# ospy_hw3_3_extensions.net
KiCad netlist of a schematic drawn in EAGLE
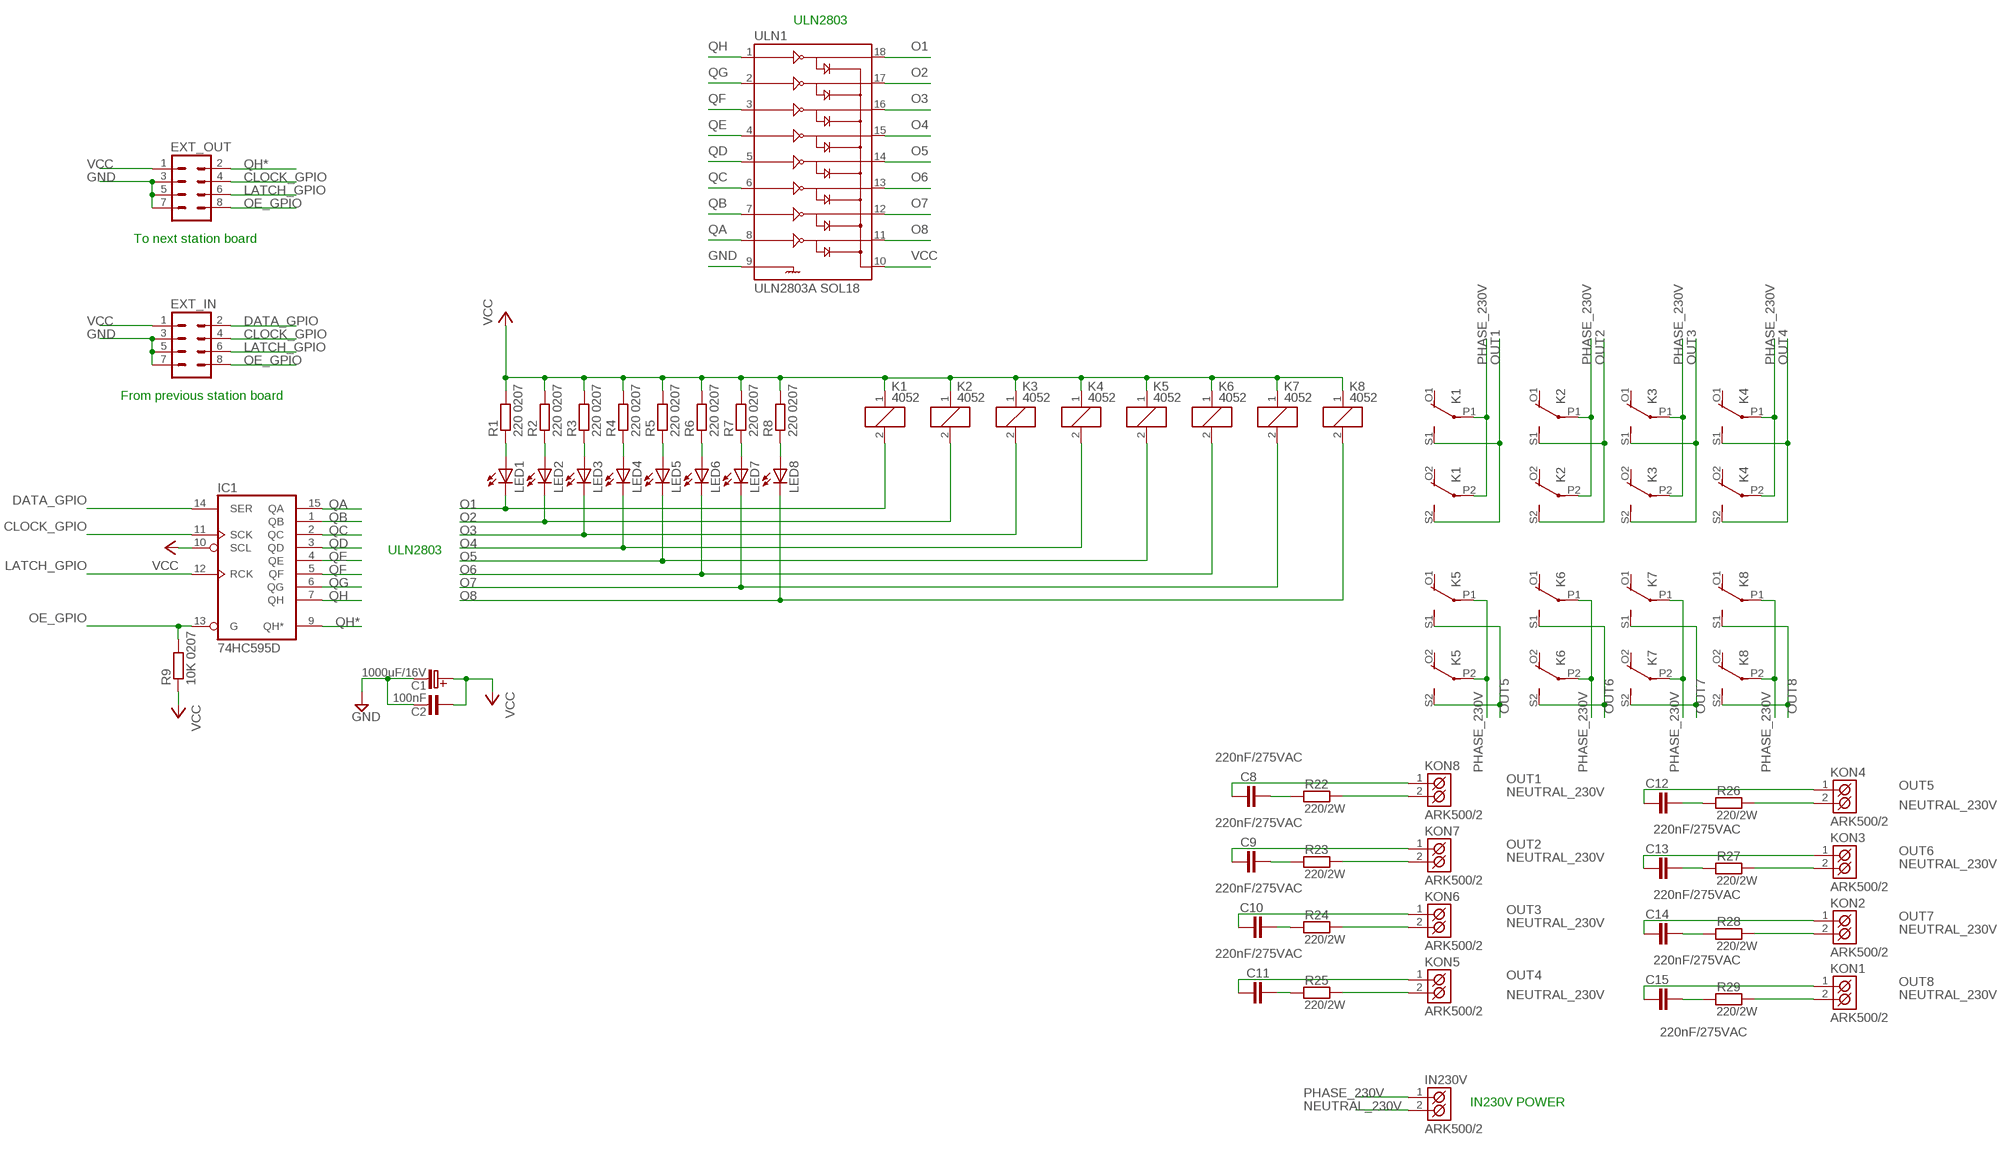
[diagram p0: schematic, sheet 1]

(export (version "E")
  (design (tool "Eeschema 10.0.6"))
  (components
    (comp (ref "C1")
      (value "1000uF/16V")
      (footprint "eagle-import:C_EL_5")
      (libsource (lib "eagle-import") (part "#_RADIAL_POUZDRA5"))
    )
    (comp (ref "C2")
      (value "100nF")
      (footprint "eagle-import:RM5_2,5")
      (libsource (lib "eagle-import") (part "100N-J/63V"))
    )
    (comp (ref "C8")
      (value "220nF/275VAC")
      (footprint "eagle-import:C225-087X268")
      (libsource (lib "eagle-import") (part "C-EU225-087X268"))
    )
    (comp (ref "C9")
      (value "220nF/275VAC")
      (footprint "eagle-import:C225-087X268")
      (libsource (lib "eagle-import") (part "C-EU225-087X268"))
    )
    (comp (ref "C10")
      (value "220nF/275VAC")
      (footprint "eagle-import:C225-087X268")
      (libsource (lib "eagle-import") (part "C-EU225-087X268"))
    )
    (comp (ref "C11")
      (value "220nF/275VAC")
      (footprint "eagle-import:C225-087X268")
      (libsource (lib "eagle-import") (part "C-EU225-087X268"))
    )
    (comp (ref "C12")
      (value "220nF/275VAC")
      (footprint "eagle-import:C225-087X268")
      (libsource (lib "eagle-import") (part "C-EU225-087X268"))
    )
    (comp (ref "C13")
      (value "220nF/275VAC")
      (footprint "eagle-import:C225-087X268")
      (libsource (lib "eagle-import") (part "C-EU225-087X268"))
    )
    (comp (ref "C14")
      (value "220nF/275VAC")
      (footprint "eagle-import:C225-087X268")
      (libsource (lib "eagle-import") (part "C-EU225-087X268"))
    )
    (comp (ref "C15")
      (value "220nF/275VAC")
      (footprint "eagle-import:C225-087X268")
      (libsource (lib "eagle-import") (part "C-EU225-087X268"))
    )
    (comp (ref "EXT_IN")
      (value "M04X2")
      (footprint "eagle-import:2X4")
      (libsource (lib "eagle-import") (part "M04X2"))
    )
    (comp (ref "EXT_OUT")
      (value "M04X2")
      (footprint "eagle-import:2X4")
      (libsource (lib "eagle-import") (part "M04X2"))
    )
    (comp (ref "IC1")
      (value "74HC595D")
      (footprint "eagle-import:SO16")
      (libsource (lib "eagle-import") (part "74595DHC"))
    )
    (comp (ref "IN230V")
      (value "ARK500/2")
      (footprint "eagle-import:ARK500_2")
      (libsource (lib "eagle-import") (part "ARK500/2"))
    )
    (comp (ref "K1")
      (value "4052")
      (footprint "eagle-import:F4052")
      (libsource (lib "eagle-import") (part "4052"))
    )
    (comp (ref "K2")
      (value "4052")
      (footprint "eagle-import:F4052")
      (libsource (lib "eagle-import") (part "4052"))
    )
    (comp (ref "K3")
      (value "4052")
      (footprint "eagle-import:F4052")
      (libsource (lib "eagle-import") (part "4052"))
    )
    (comp (ref "K4")
      (value "4052")
      (footprint "eagle-import:F4052")
      (libsource (lib "eagle-import") (part "4052"))
    )
    (comp (ref "K5")
      (value "4052")
      (footprint "eagle-import:F4052")
      (libsource (lib "eagle-import") (part "4052"))
    )
    (comp (ref "K6")
      (value "4052")
      (footprint "eagle-import:F4052")
      (libsource (lib "eagle-import") (part "4052"))
    )
    (comp (ref "K7")
      (value "4052")
      (footprint "eagle-import:F4052")
      (libsource (lib "eagle-import") (part "4052"))
    )
    (comp (ref "K8")
      (value "4052")
      (footprint "eagle-import:F4052")
      (libsource (lib "eagle-import") (part "4052"))
    )
    (comp (ref "KON1")
      (value "ARK500/2")
      (footprint "eagle-import:ARK500_2")
      (libsource (lib "eagle-import") (part "ARK500/2"))
    )
    (comp (ref "KON2")
      (value "ARK500/2")
      (footprint "eagle-import:ARK500_2")
      (libsource (lib "eagle-import") (part "ARK500/2"))
    )
    (comp (ref "KON3")
      (value "ARK500/2")
      (footprint "eagle-import:ARK500_2")
      (libsource (lib "eagle-import") (part "ARK500/2"))
    )
    (comp (ref "KON4")
      (value "ARK500/2")
      (footprint "eagle-import:ARK500_2")
      (libsource (lib "eagle-import") (part "ARK500/2"))
    )
    (comp (ref "KON5")
      (value "ARK500/2")
      (footprint "eagle-import:ARK500_2")
      (libsource (lib "eagle-import") (part "ARK500/2"))
    )
    (comp (ref "KON6")
      (value "ARK500/2")
      (footprint "eagle-import:ARK500_2")
      (libsource (lib "eagle-import") (part "ARK500/2"))
    )
    (comp (ref "KON7")
      (value "ARK500/2")
      (footprint "eagle-import:ARK500_2")
      (libsource (lib "eagle-import") (part "ARK500/2"))
    )
    (comp (ref "KON8")
      (value "ARK500/2")
      (footprint "eagle-import:ARK500_2")
      (libsource (lib "eagle-import") (part "ARK500/2"))
    )
    (comp (ref "LED1")
      (value "LED3MM")
      (footprint "eagle-import:LED3MM")
      (libsource (lib "eagle-import") (part "LED3MM"))
    )
    (comp (ref "LED2")
      (value "LED3MM")
      (footprint "eagle-import:LED3MM")
      (libsource (lib "eagle-import") (part "LED3MM"))
    )
    (comp (ref "LED3")
      (value "LED3MM")
      (footprint "eagle-import:LED3MM")
      (libsource (lib "eagle-import") (part "LED3MM"))
    )
    (comp (ref "LED4")
      (value "LED3MM")
      (footprint "eagle-import:LED3MM")
      (libsource (lib "eagle-import") (part "LED3MM"))
    )
    (comp (ref "LED5")
      (value "LED3MM")
      (footprint "eagle-import:LED3MM")
      (libsource (lib "eagle-import") (part "LED3MM"))
    )
    (comp (ref "LED6")
      (value "LED3MM")
      (footprint "eagle-import:LED3MM")
      (libsource (lib "eagle-import") (part "LED3MM"))
    )
    (comp (ref "LED7")
      (value "LED3MM")
      (footprint "eagle-import:LED3MM")
      (libsource (lib "eagle-import") (part "LED3MM"))
    )
    (comp (ref "LED8")
      (value "LED3MM")
      (footprint "eagle-import:LED3MM")
      (libsource (lib "eagle-import") (part "LED3MM"))
    )
    (comp (ref "R1")
      (value "220 0207")
      (footprint "eagle-import:0207_10")
      (libsource (lib "eagle-import") (part "R-EU_0207/10"))
    )
    (comp (ref "R2")
      (value "220 0207")
      (footprint "eagle-import:0207_10")
      (libsource (lib "eagle-import") (part "R-EU_0207/10"))
    )
    (comp (ref "R3")
      (value "220 0207")
      (footprint "eagle-import:0207_10")
      (libsource (lib "eagle-import") (part "R-EU_0207/10"))
    )
    (comp (ref "R4")
      (value "220 0207")
      (footprint "eagle-import:0207_10")
      (libsource (lib "eagle-import") (part "R-EU_0207/10"))
    )
    (comp (ref "R5")
      (value "220 0207")
      (footprint "eagle-import:0207_10")
      (libsource (lib "eagle-import") (part "R-EU_0207/10"))
    )
    (comp (ref "R6")
      (value "220 0207")
      (footprint "eagle-import:0207_10")
      (libsource (lib "eagle-import") (part "R-EU_0207/10"))
    )
    (comp (ref "R7")
      (value "220 0207")
      (footprint "eagle-import:0207_10")
      (libsource (lib "eagle-import") (part "R-EU_0207/10"))
    )
    (comp (ref "R8")
      (value "220 0207")
      (footprint "eagle-import:0207_10")
      (libsource (lib "eagle-import") (part "R-EU_0207/10"))
    )
    (comp (ref "R9")
      (value "10K 0207")
      (footprint "eagle-import:0207_10")
      (libsource (lib "eagle-import") (part "R-EU_0207/10"))
    )
    (comp (ref "R22")
      (value "220/2W")
      (footprint "eagle-import:R__2W")
      (libsource (lib "eagle-import") (part "W2_220R"))
    )
    (comp (ref "R23")
      (value "220/2W")
      (footprint "eagle-import:R__2W")
      (libsource (lib "eagle-import") (part "W2_220R"))
    )
    (comp (ref "R24")
      (value "220/2W")
      (footprint "eagle-import:R__2W")
      (libsource (lib "eagle-import") (part "W2_220R"))
    )
    (comp (ref "R25")
      (value "220/2W")
      (footprint "eagle-import:R__2W")
      (libsource (lib "eagle-import") (part "W2_220R"))
    )
    (comp (ref "R26")
      (value "220/2W")
      (footprint "eagle-import:R__2W")
      (libsource (lib "eagle-import") (part "W2_220R"))
    )
    (comp (ref "R27")
      (value "220/2W")
      (footprint "eagle-import:R__2W")
      (libsource (lib "eagle-import") (part "W2_220R"))
    )
    (comp (ref "R28")
      (value "220/2W")
      (footprint "eagle-import:R__2W")
      (libsource (lib "eagle-import") (part "W2_220R"))
    )
    (comp (ref "R29")
      (value "220/2W")
      (footprint "eagle-import:R__2W")
      (libsource (lib "eagle-import") (part "W2_220R"))
    )
    (comp (ref "ULN1")
      (value "ULN2803A SOL18")
      (footprint "eagle-import:SO18L")
      (libsource (lib "eagle-import") (part "ULN2803SOICW"))
    )
  )
  (nets
    (net (code "1") (name "/CLOCK_GPIO") (class "Default")
      (node (ref "EXT_IN") (pin "4") (pinfunction "4_4") (pintype "passive"))
      (node (ref "EXT_OUT") (pin "4") (pinfunction "4_4") (pintype "passive"))
      (node (ref "IC1") (pin "11") (pinfunction "SCK_11") (pintype "input"))
    )
    (net (code "2") (name "/DATA_GPIO") (class "Default")
      (node (ref "EXT_IN") (pin "2") (pinfunction "2_2") (pintype "passive"))
      (node (ref "IC1") (pin "14") (pinfunction "SER_14") (pintype "input"))
    )
    (net (code "3") (name "/LATCH_GPIO") (class "Default")
      (node (ref "EXT_IN") (pin "6") (pinfunction "6_6") (pintype "passive"))
      (node (ref "EXT_OUT") (pin "6") (pinfunction "6_6") (pintype "passive"))
      (node (ref "IC1") (pin "12") (pinfunction "RCK_12") (pintype "input"))
    )
    (net (code "4") (name "/NEUTRAL_230V") (class "Default")
      (node (ref "IN230V") (pin "2") (pinfunction "K2_2") (pintype "passive"))
      (node (ref "KON1") (pin "2") (pinfunction "K2_2") (pintype "passive"))
      (node (ref "KON2") (pin "2") (pinfunction "K2_2") (pintype "passive"))
      (node (ref "KON3") (pin "2") (pinfunction "K2_2") (pintype "passive"))
      (node (ref "KON4") (pin "2") (pinfunction "K2_2") (pintype "passive"))
      (node (ref "KON5") (pin "2") (pinfunction "K2_2") (pintype "passive"))
      (node (ref "KON6") (pin "2") (pinfunction "K2_2") (pintype "passive"))
      (node (ref "KON7") (pin "2") (pinfunction "K2_2") (pintype "passive"))
      (node (ref "KON8") (pin "2") (pinfunction "K2_2") (pintype "passive"))
      (node (ref "R22") (pin "2") (pinfunction "2_2") (pintype "passive"))
      (node (ref "R23") (pin "2") (pinfunction "2_2") (pintype "passive"))
      (node (ref "R24") (pin "2") (pinfunction "2_2") (pintype "passive"))
      (node (ref "R25") (pin "2") (pinfunction "2_2") (pintype "passive"))
      (node (ref "R26") (pin "2") (pinfunction "2_2") (pintype "passive"))
      (node (ref "R27") (pin "2") (pinfunction "2_2") (pintype "passive"))
      (node (ref "R28") (pin "2") (pinfunction "2_2") (pintype "passive"))
      (node (ref "R29") (pin "2") (pinfunction "2_2") (pintype "passive"))
    )
    (net (code "5") (name "/O1") (class "Default")
      (node (ref "K1") (pin "2") (pinfunction "2_2") (pintype "passive"))
      (node (ref "LED1") (pin "K") (pinfunction "C_K") (pintype "passive"))
      (node (ref "ULN1") (pin "18") (pinfunction "18_18") (pintype "bidirectional"))
    )
    (net (code "6") (name "/O2") (class "Default")
      (node (ref "K2") (pin "2") (pinfunction "2_2") (pintype "passive"))
      (node (ref "LED2") (pin "K") (pinfunction "C_K") (pintype "passive"))
      (node (ref "ULN1") (pin "17") (pinfunction "17_17") (pintype "bidirectional"))
    )
    (net (code "7") (name "/O3") (class "Default")
      (node (ref "K3") (pin "2") (pinfunction "2_2") (pintype "passive"))
      (node (ref "LED3") (pin "K") (pinfunction "C_K") (pintype "passive"))
      (node (ref "ULN1") (pin "16") (pinfunction "16_16") (pintype "bidirectional"))
    )
    (net (code "8") (name "/O4") (class "Default")
      (node (ref "K4") (pin "2") (pinfunction "2_2") (pintype "passive"))
      (node (ref "LED4") (pin "K") (pinfunction "C_K") (pintype "passive"))
      (node (ref "ULN1") (pin "15") (pinfunction "15_15") (pintype "bidirectional"))
    )
    (net (code "9") (name "/O5") (class "Default")
      (node (ref "K5") (pin "2") (pinfunction "2_2") (pintype "passive"))
      (node (ref "LED5") (pin "K") (pinfunction "C_K") (pintype "passive"))
      (node (ref "ULN1") (pin "14") (pinfunction "14_14") (pintype "bidirectional"))
    )
    (net (code "10") (name "/O6") (class "Default")
      (node (ref "K6") (pin "2") (pinfunction "2_2") (pintype "passive"))
      (node (ref "LED6") (pin "K") (pinfunction "C_K") (pintype "passive"))
      (node (ref "ULN1") (pin "13") (pinfunction "13_13") (pintype "bidirectional"))
    )
    (net (code "11") (name "/O7") (class "Default")
      (node (ref "K7") (pin "2") (pinfunction "2_2") (pintype "passive"))
      (node (ref "LED7") (pin "K") (pinfunction "C_K") (pintype "passive"))
      (node (ref "ULN1") (pin "12") (pinfunction "12_12") (pintype "bidirectional"))
    )
    (net (code "12") (name "/O8") (class "Default")
      (node (ref "K8") (pin "2") (pinfunction "2_2") (pintype "passive"))
      (node (ref "LED8") (pin "K") (pinfunction "C_K") (pintype "passive"))
      (node (ref "ULN1") (pin "11") (pinfunction "11_11") (pintype "bidirectional"))
    )
    (net (code "13") (name "/OE_GPIO") (class "Default")
      (node (ref "EXT_IN") (pin "8") (pinfunction "8_8") (pintype "passive"))
      (node (ref "EXT_OUT") (pin "8") (pinfunction "8_8") (pintype "passive"))
      (node (ref "IC1") (pin "13") (pinfunction "G_13") (pintype "input"))
      (node (ref "R9") (pin "2") (pinfunction "2_2") (pintype "passive"))
    )
    (net (code "14") (name "/OUT1") (class "Default")
      (node (ref "C8") (pin "1") (pinfunction "1_1") (pintype "passive"))
      (node (ref "K1") (pin "S1") (pinfunction "S_S1") (pintype "passive"))
      (node (ref "K1") (pin "S2") (pinfunction "S_S2") (pintype "passive"))
      (node (ref "KON8") (pin "1") (pinfunction "K1_1") (pintype "passive"))
    )
    (net (code "15") (name "/OUT2") (class "Default")
      (node (ref "C9") (pin "1") (pinfunction "1_1") (pintype "passive"))
      (node (ref "K2") (pin "S1") (pinfunction "S_S1") (pintype "passive"))
      (node (ref "K2") (pin "S2") (pinfunction "S_S2") (pintype "passive"))
      (node (ref "KON7") (pin "1") (pinfunction "K1_1") (pintype "passive"))
    )
    (net (code "16") (name "/OUT3") (class "Default")
      (node (ref "C10") (pin "1") (pinfunction "1_1") (pintype "passive"))
      (node (ref "K3") (pin "S1") (pinfunction "S_S1") (pintype "passive"))
      (node (ref "K3") (pin "S2") (pinfunction "S_S2") (pintype "passive"))
      (node (ref "KON6") (pin "1") (pinfunction "K1_1") (pintype "passive"))
    )
    (net (code "17") (name "/OUT4") (class "Default")
      (node (ref "C11") (pin "1") (pinfunction "1_1") (pintype "passive"))
      (node (ref "K4") (pin "S1") (pinfunction "S_S1") (pintype "passive"))
      (node (ref "K4") (pin "S2") (pinfunction "S_S2") (pintype "passive"))
      (node (ref "KON5") (pin "1") (pinfunction "K1_1") (pintype "passive"))
    )
    (net (code "18") (name "/OUT5") (class "Default")
      (node (ref "C12") (pin "1") (pinfunction "1_1") (pintype "passive"))
      (node (ref "K5") (pin "S1") (pinfunction "S_S1") (pintype "passive"))
      (node (ref "K5") (pin "S2") (pinfunction "S_S2") (pintype "passive"))
      (node (ref "KON4") (pin "1") (pinfunction "K1_1") (pintype "passive"))
    )
    (net (code "19") (name "/OUT6") (class "Default")
      (node (ref "C13") (pin "1") (pinfunction "1_1") (pintype "passive"))
      (node (ref "K6") (pin "S1") (pinfunction "S_S1") (pintype "passive"))
      (node (ref "K6") (pin "S2") (pinfunction "S_S2") (pintype "passive"))
      (node (ref "KON3") (pin "1") (pinfunction "K1_1") (pintype "passive"))
    )
    (net (code "20") (name "/OUT7") (class "Default")
      (node (ref "C14") (pin "1") (pinfunction "1_1") (pintype "passive"))
      (node (ref "K7") (pin "S1") (pinfunction "S_S1") (pintype "passive"))
      (node (ref "K7") (pin "S2") (pinfunction "S_S2") (pintype "passive"))
      (node (ref "KON2") (pin "1") (pinfunction "K1_1") (pintype "passive"))
    )
    (net (code "21") (name "/OUT8") (class "Default")
      (node (ref "C15") (pin "1") (pinfunction "1_1") (pintype "passive"))
      (node (ref "K8") (pin "S1") (pinfunction "S_S1") (pintype "passive"))
      (node (ref "K8") (pin "S2") (pinfunction "S_S2") (pintype "passive"))
      (node (ref "KON1") (pin "1") (pinfunction "K1_1") (pintype "passive"))
    )
    (net (code "22") (name "/PHASE_230V") (class "Default")
      (node (ref "IN230V") (pin "1") (pinfunction "K1_1") (pintype "passive"))
      (node (ref "K1") (pin "P1") (pinfunction "P_P1") (pintype "passive"))
      (node (ref "K1") (pin "P2") (pinfunction "P_P2") (pintype "passive"))
      (node (ref "K2") (pin "P1") (pinfunction "P_P1") (pintype "passive"))
      (node (ref "K2") (pin "P2") (pinfunction "P_P2") (pintype "passive"))
      (node (ref "K3") (pin "P1") (pinfunction "P_P1") (pintype "passive"))
      (node (ref "K3") (pin "P2") (pinfunction "P_P2") (pintype "passive"))
      (node (ref "K4") (pin "P1") (pinfunction "P_P1") (pintype "passive"))
      (node (ref "K4") (pin "P2") (pinfunction "P_P2") (pintype "passive"))
      (node (ref "K5") (pin "P1") (pinfunction "P_P1") (pintype "passive"))
      (node (ref "K5") (pin "P2") (pinfunction "P_P2") (pintype "passive"))
      (node (ref "K6") (pin "P1") (pinfunction "P_P1") (pintype "passive"))
      (node (ref "K6") (pin "P2") (pinfunction "P_P2") (pintype "passive"))
      (node (ref "K7") (pin "P1") (pinfunction "P_P1") (pintype "passive"))
      (node (ref "K7") (pin "P2") (pinfunction "P_P2") (pintype "passive"))
      (node (ref "K8") (pin "P1") (pinfunction "P_P1") (pintype "passive"))
      (node (ref "K8") (pin "P2") (pinfunction "P_P2") (pintype "passive"))
    )
    (net (code "23") (name "/QA") (class "Default")
      (node (ref "IC1") (pin "15") (pinfunction "QA_15") (pintype "tri_state"))
      (node (ref "ULN1") (pin "8") (pinfunction "8_8") (pintype "bidirectional"))
    )
    (net (code "24") (name "/QB") (class "Default")
      (node (ref "IC1") (pin "1") (pinfunction "QB_1") (pintype "tri_state"))
      (node (ref "ULN1") (pin "7") (pinfunction "7_7") (pintype "bidirectional"))
    )
    (net (code "25") (name "/QC") (class "Default")
      (node (ref "IC1") (pin "2") (pinfunction "QC_2") (pintype "tri_state"))
      (node (ref "ULN1") (pin "6") (pinfunction "6_6") (pintype "bidirectional"))
    )
    (net (code "26") (name "/QD") (class "Default")
      (node (ref "IC1") (pin "3") (pinfunction "QD_3") (pintype "tri_state"))
      (node (ref "ULN1") (pin "5") (pinfunction "5_5") (pintype "bidirectional"))
    )
    (net (code "27") (name "/QE") (class "Default")
      (node (ref "IC1") (pin "4") (pinfunction "QE_4") (pintype "tri_state"))
      (node (ref "ULN1") (pin "4") (pinfunction "4_4") (pintype "bidirectional"))
    )
    (net (code "28") (name "/QF") (class "Default")
      (node (ref "IC1") (pin "5") (pinfunction "QF_5") (pintype "tri_state"))
      (node (ref "ULN1") (pin "3") (pinfunction "3_3") (pintype "bidirectional"))
    )
    (net (code "29") (name "/QG") (class "Default")
      (node (ref "IC1") (pin "6") (pinfunction "QG_6") (pintype "tri_state"))
      (node (ref "ULN1") (pin "2") (pinfunction "2_2") (pintype "bidirectional"))
    )
    (net (code "30") (name "/QH") (class "Default")
      (node (ref "IC1") (pin "7") (pinfunction "QH_7") (pintype "tri_state"))
      (node (ref "ULN1") (pin "1") (pinfunction "1_1") (pintype "bidirectional"))
    )
    (net (code "31") (name "/QH*") (class "Default")
      (node (ref "EXT_OUT") (pin "2") (pinfunction "2_2") (pintype "passive"))
      (node (ref "IC1") (pin "9") (pinfunction "QH*_9") (pintype "tri_state"))
    )
    (net (code "32") (name "GND") (class "Default")
      (node (ref "C1") (pin "C-") (pinfunction "C_EL-_C-") (pintype "passive"))
      (node (ref "C2") (pin "2") (pinfunction "2_2") (pintype "passive"))
      (node (ref "EXT_IN") (pin "3") (pinfunction "3_3") (pintype "passive"))
      (node (ref "EXT_IN") (pin "5") (pinfunction "5_5") (pintype "passive"))
      (node (ref "EXT_IN") (pin "7") (pinfunction "7_7") (pintype "passive"))
      (node (ref "EXT_OUT") (pin "3") (pinfunction "3_3") (pintype "passive"))
      (node (ref "EXT_OUT") (pin "5") (pinfunction "5_5") (pintype "passive"))
      (node (ref "EXT_OUT") (pin "7") (pinfunction "7_7") (pintype "passive"))
      (node (ref "ULN1") (pin "9") (pinfunction "9_9") (pintype "bidirectional"))
    )
    (net (code "33") (name "Net-(C8-Pad2)") (class "Default")
      (node (ref "C8") (pin "2") (pinfunction "2_2") (pintype "passive"))
      (node (ref "R22") (pin "1") (pinfunction "1_1") (pintype "passive"))
    )
    (net (code "34") (name "Net-(C9-Pad2)") (class "Default")
      (node (ref "C9") (pin "2") (pinfunction "2_2") (pintype "passive"))
      (node (ref "R23") (pin "1") (pinfunction "1_1") (pintype "passive"))
    )
    (net (code "35") (name "Net-(C10-Pad2)") (class "Default")
      (node (ref "C10") (pin "2") (pinfunction "2_2") (pintype "passive"))
      (node (ref "R24") (pin "1") (pinfunction "1_1") (pintype "passive"))
    )
    (net (code "36") (name "Net-(C11-Pad2)") (class "Default")
      (node (ref "C11") (pin "2") (pinfunction "2_2") (pintype "passive"))
      (node (ref "R25") (pin "1") (pinfunction "1_1") (pintype "passive"))
    )
    (net (code "37") (name "Net-(C12-Pad2)") (class "Default")
      (node (ref "C12") (pin "2") (pinfunction "2_2") (pintype "passive"))
      (node (ref "R26") (pin "1") (pinfunction "1_1") (pintype "passive"))
    )
    (net (code "38") (name "Net-(C13-Pad2)") (class "Default")
      (node (ref "C13") (pin "2") (pinfunction "2_2") (pintype "passive"))
      (node (ref "R27") (pin "1") (pinfunction "1_1") (pintype "passive"))
    )
    (net (code "39") (name "Net-(C14-Pad2)") (class "Default")
      (node (ref "C14") (pin "2") (pinfunction "2_2") (pintype "passive"))
      (node (ref "R28") (pin "1") (pinfunction "1_1") (pintype "passive"))
    )
    (net (code "40") (name "Net-(C15-Pad2)") (class "Default")
      (node (ref "C15") (pin "2") (pinfunction "2_2") (pintype "passive"))
      (node (ref "R29") (pin "1") (pinfunction "1_1") (pintype "passive"))
    )
    (net (code "41") (name "Net-(LED1-PadA)") (class "Default")
      (node (ref "LED1") (pin "A") (pinfunction "A_A") (pintype "passive"))
      (node (ref "R1") (pin "1") (pinfunction "1_1") (pintype "passive"))
    )
    (net (code "42") (name "Net-(LED2-PadA)") (class "Default")
      (node (ref "LED2") (pin "A") (pinfunction "A_A") (pintype "passive"))
      (node (ref "R2") (pin "1") (pinfunction "1_1") (pintype "passive"))
    )
    (net (code "43") (name "Net-(LED3-PadA)") (class "Default")
      (node (ref "LED3") (pin "A") (pinfunction "A_A") (pintype "passive"))
      (node (ref "R3") (pin "1") (pinfunction "1_1") (pintype "passive"))
    )
    (net (code "44") (name "Net-(LED4-PadA)") (class "Default")
      (node (ref "LED4") (pin "A") (pinfunction "A_A") (pintype "passive"))
      (node (ref "R4") (pin "1") (pinfunction "1_1") (pintype "passive"))
    )
    (net (code "45") (name "Net-(LED5-PadA)") (class "Default")
      (node (ref "LED5") (pin "A") (pinfunction "A_A") (pintype "passive"))
      (node (ref "R5") (pin "1") (pinfunction "1_1") (pintype "passive"))
    )
    (net (code "46") (name "Net-(LED6-PadA)") (class "Default")
      (node (ref "LED6") (pin "A") (pinfunction "A_A") (pintype "passive"))
      (node (ref "R6") (pin "1") (pinfunction "1_1") (pintype "passive"))
    )
    (net (code "47") (name "Net-(LED7-PadA)") (class "Default")
      (node (ref "LED7") (pin "A") (pinfunction "A_A") (pintype "passive"))
      (node (ref "R7") (pin "1") (pinfunction "1_1") (pintype "passive"))
    )
    (net (code "48") (name "Net-(LED8-PadA)") (class "Default")
      (node (ref "LED8") (pin "A") (pinfunction "A_A") (pintype "passive"))
      (node (ref "R8") (pin "1") (pinfunction "1_1") (pintype "passive"))
    )
    (net (code "49") (name "VCC") (class "Default")
      (node (ref "C1") (pin "C+") (pinfunction "C_EL+_C+") (pintype "passive"))
      (node (ref "C2") (pin "1") (pinfunction "1_1") (pintype "passive"))
      (node (ref "EXT_IN") (pin "1") (pinfunction "1_1") (pintype "passive"))
      (node (ref "EXT_OUT") (pin "1") (pinfunction "1_1") (pintype "passive"))
      (node (ref "IC1") (pin "10") (pinfunction "SCL_10") (pintype "input"))
      (node (ref "K1") (pin "1") (pinfunction "1_1") (pintype "passive"))
      (node (ref "K2") (pin "1") (pinfunction "1_1") (pintype "passive"))
      (node (ref "K3") (pin "1") (pinfunction "1_1") (pintype "passive"))
      (node (ref "K4") (pin "1") (pinfunction "1_1") (pintype "passive"))
      (node (ref "K5") (pin "1") (pinfunction "1_1") (pintype "passive"))
      (node (ref "K6") (pin "1") (pinfunction "1_1") (pintype "passive"))
      (node (ref "K7") (pin "1") (pinfunction "1_1") (pintype "passive"))
      (node (ref "K8") (pin "1") (pinfunction "1_1") (pintype "passive"))
      (node (ref "R1") (pin "2") (pinfunction "2_2") (pintype "passive"))
      (node (ref "R2") (pin "2") (pinfunction "2_2") (pintype "passive"))
      (node (ref "R3") (pin "2") (pinfunction "2_2") (pintype "passive"))
      (node (ref "R4") (pin "2") (pinfunction "2_2") (pintype "passive"))
      (node (ref "R5") (pin "2") (pinfunction "2_2") (pintype "passive"))
      (node (ref "R6") (pin "2") (pinfunction "2_2") (pintype "passive"))
      (node (ref "R7") (pin "2") (pinfunction "2_2") (pintype "passive"))
      (node (ref "R8") (pin "2") (pinfunction "2_2") (pintype "passive"))
      (node (ref "R9") (pin "1") (pinfunction "1_1") (pintype "passive"))
      (node (ref "ULN1") (pin "10") (pinfunction "10_10") (pintype "bidirectional"))
    )
    (net (code "50") (name "unconnected-(K1B-O-PadO1)") (class "Default")
      (node (ref "K1") (pin "O1") (pinfunction "O_O1") (pintype "passive"))
    )
    (net (code "51") (name "unconnected-(K1C-O-PadO2)") (class "Default")
      (node (ref "K1") (pin "O2") (pinfunction "O_O2") (pintype "passive"))
    )
    (net (code "52") (name "unconnected-(K2B-O-PadO1)") (class "Default")
      (node (ref "K2") (pin "O1") (pinfunction "O_O1") (pintype "passive"))
    )
    (net (code "53") (name "unconnected-(K2C-O-PadO2)") (class "Default")
      (node (ref "K2") (pin "O2") (pinfunction "O_O2") (pintype "passive"))
    )
    (net (code "54") (name "unconnected-(K3B-O-PadO1)") (class "Default")
      (node (ref "K3") (pin "O1") (pinfunction "O_O1") (pintype "passive"))
    )
    (net (code "55") (name "unconnected-(K3C-O-PadO2)") (class "Default")
      (node (ref "K3") (pin "O2") (pinfunction "O_O2") (pintype "passive"))
    )
    (net (code "56") (name "unconnected-(K4B-O-PadO1)") (class "Default")
      (node (ref "K4") (pin "O1") (pinfunction "O_O1") (pintype "passive"))
    )
    (net (code "57") (name "unconnected-(K4C-O-PadO2)") (class "Default")
      (node (ref "K4") (pin "O2") (pinfunction "O_O2") (pintype "passive"))
    )
    (net (code "58") (name "unconnected-(K5B-O-PadO1)") (class "Default")
      (node (ref "K5") (pin "O1") (pinfunction "O_O1") (pintype "passive"))
    )
    (net (code "59") (name "unconnected-(K5C-O-PadO2)") (class "Default")
      (node (ref "K5") (pin "O2") (pinfunction "O_O2") (pintype "passive"))
    )
    (net (code "60") (name "unconnected-(K6B-O-PadO1)") (class "Default")
      (node (ref "K6") (pin "O1") (pinfunction "O_O1") (pintype "passive"))
    )
    (net (code "61") (name "unconnected-(K6C-O-PadO2)") (class "Default")
      (node (ref "K6") (pin "O2") (pinfunction "O_O2") (pintype "passive"))
    )
    (net (code "62") (name "unconnected-(K7B-O-PadO1)") (class "Default")
      (node (ref "K7") (pin "O1") (pinfunction "O_O1") (pintype "passive"))
    )
    (net (code "63") (name "unconnected-(K7C-O-PadO2)") (class "Default")
      (node (ref "K7") (pin "O2") (pinfunction "O_O2") (pintype "passive"))
    )
    (net (code "64") (name "unconnected-(K8B-O-PadO1)") (class "Default")
      (node (ref "K8") (pin "O1") (pinfunction "O_O1") (pintype "passive"))
    )
    (net (code "65") (name "unconnected-(K8C-O-PadO2)") (class "Default")
      (node (ref "K8") (pin "O2") (pinfunction "O_O2") (pintype "passive"))
    )
  )
)
